# table4_vd3.net
KiCad netlist of a schematic drawn in EasyEDA
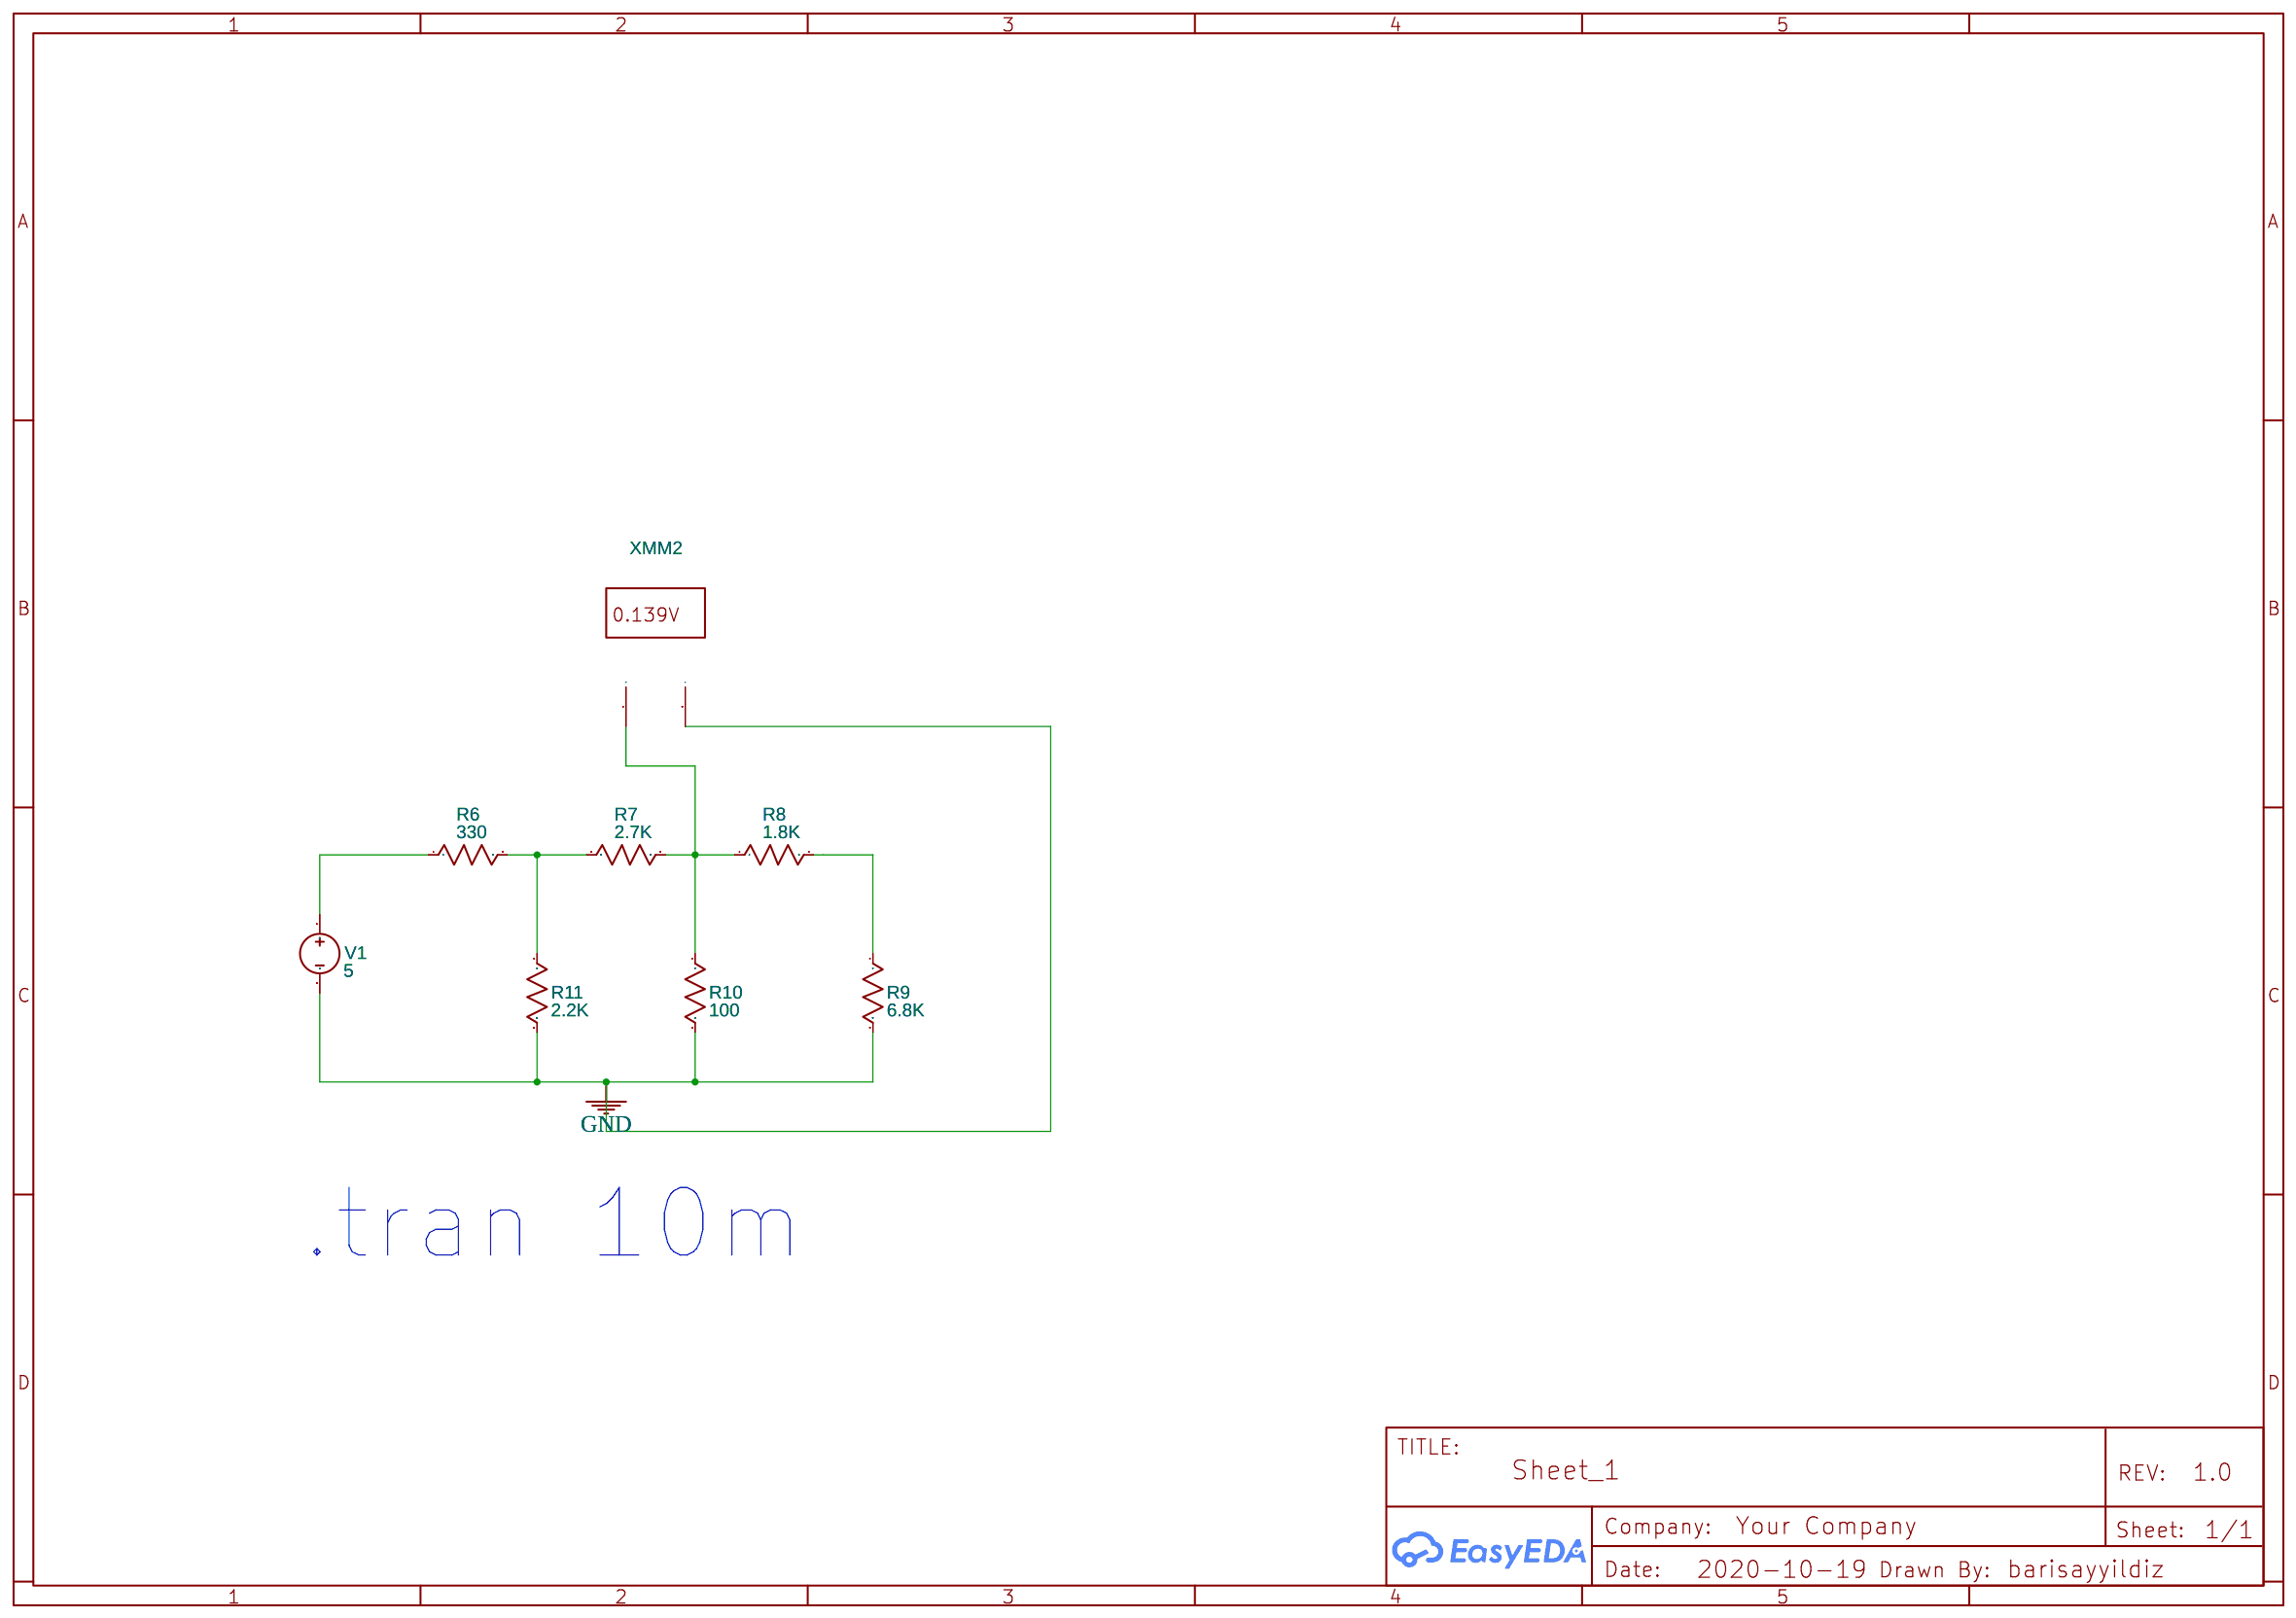
[diagram p0: schematic sheet]

(export (version "E")
  (design (tool "Eeschema 10.0.6"))
  (components
    (comp (ref "R6") (value "330") (libsource (lib "") (part "Resistor_US")))
    (comp (ref "R7") (value "2.7K") (libsource (lib "") (part "Resistor_US")))
    (comp (ref "R8") (value "1.8K") (libsource (lib "") (part "Resistor_US")))
    (comp (ref "R9") (value "6.8K") (libsource (lib "") (part "Resistor_US_1")))
    (comp (ref "R10") (value "100") (libsource (lib "") (part "Resistor_US_1")))
    (comp (ref "R11") (value "2.2K") (libsource (lib "") (part "Resistor_US_1")))
    (comp (ref "V1") (value "5") (libsource (lib "") (part "VDC")))
    (comp (ref "XMM2") (value "Multimeter") (libsource (lib "") (part "MULTIMETER")))
  )
  (nets
    (net (code "1") (name "GND") (class "Default")
      (node (ref "R10") (pin "2") (pinfunction "2_2") (pintype "unspecified"))
      (node (ref "R11") (pin "2") (pinfunction "2_2") (pintype "unspecified"))
      (node (ref "R9") (pin "2") (pinfunction "2_2") (pintype "unspecified"))
      (node (ref "V1") (pin "2") (pinfunction "2_2") (pintype "unspecified"))
      (node (ref "XMM2") (pin "2") (pinfunction "I_2") (pintype "unspecified"))
    )
    (net (code "2") (name "Net-(R6-Pad1)") (class "Default")
      (node (ref "R6") (pin "1") (pinfunction "1_1") (pintype "unspecified"))
      (node (ref "V1") (pin "1") (pinfunction "1_1") (pintype "unspecified"))
    )
    (net (code "3") (name "Net-(R8-Pad2)") (class "Default")
      (node (ref "R8") (pin "2") (pinfunction "2_2") (pintype "unspecified"))
      (node (ref "R9") (pin "1") (pinfunction "1_1") (pintype "unspecified"))
    )
    (net (code "4") (name "Net-(R11-Pad1)") (class "Default")
      (node (ref "R11") (pin "1") (pinfunction "1_1") (pintype "unspecified"))
      (node (ref "R6") (pin "2") (pinfunction "2_2") (pintype "unspecified"))
      (node (ref "R7") (pin "1") (pinfunction "1_1") (pintype "unspecified"))
    )
    (net (code "5") (name "Net-(XMM2-+)") (class "Default")
      (node (ref "R10") (pin "1") (pinfunction "1_1") (pintype "unspecified"))
      (node (ref "R7") (pin "2") (pinfunction "2_2") (pintype "unspecified"))
      (node (ref "R8") (pin "1") (pinfunction "1_1") (pintype "unspecified"))
      (node (ref "XMM2") (pin "1") (pinfunction "+_1") (pintype "unspecified"))
    )
  )
)
